# H0AR6_Frontend.net
KiCad netlist of a schematic drawn in Altium Designer
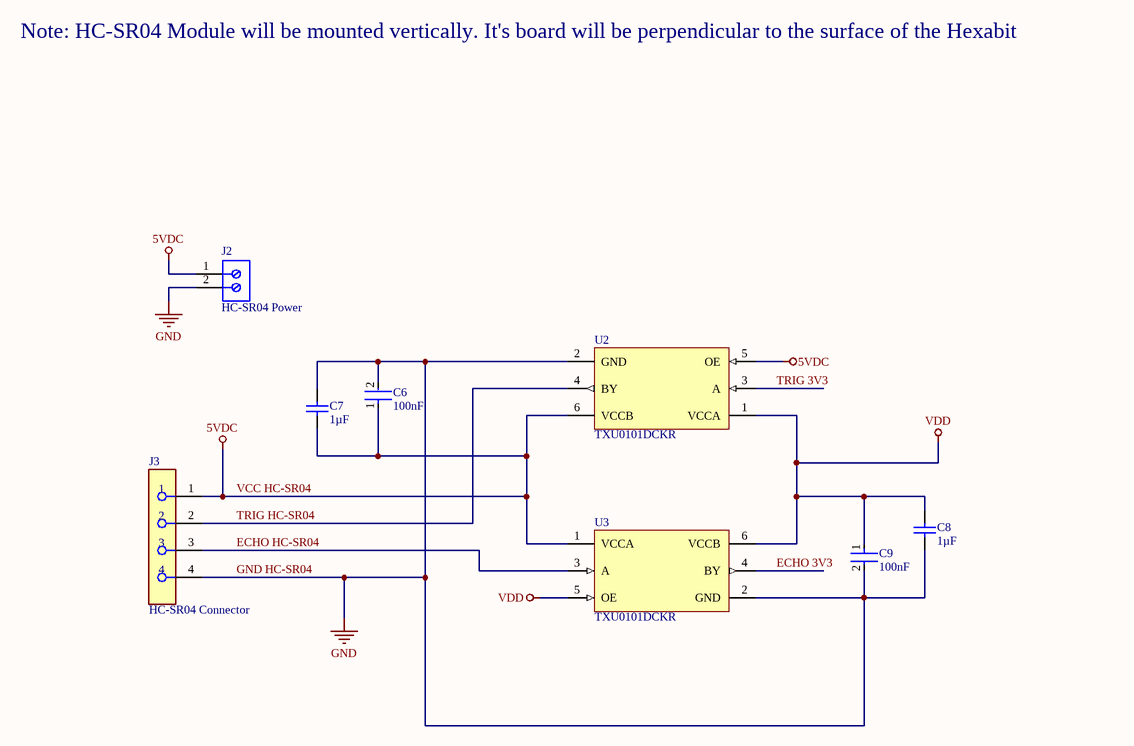
[diagram p0: H0AR6_Frontend.SchDoc]

(export (version "E")
  (design (tool "Eeschema 10.0.6"))
  (components
    (comp (ref "C6")
      (value "100nF")
      (footprint "FP-0603-L_1_6_0_15-W_0_81-MFG")
      (description "General Purpose Ceramic Capacitor, 0603, 100nF, 10%, X7R, 15%, 50V")
      (fields (field (name "TOLERANCE") "10%") (field (name "VOLTAGE") "50V"))
      (libsource (lib "Altium Content Vault") (part "02cd4be3c70576c341d710602a673aa"))
    )
    (comp (ref "C7")
      (value "1µF")
      (footprint "CAPC1608X90X35LL15T15")
      (fields
        (field (name "MANUFACTURER") "Kemet")
        (field (name "PART NUMBER") "C0603C105K4RACTU")
        (field (name "TOLERANCE") "10%")
      )
      (libsource (lib "Altium Content Vault") (part "CAP"))
    )
    (comp (ref "C8")
      (value "1µF")
      (footprint "CAPC1608X90X35LL15T15")
      (fields
        (field (name "MANUFACTURER") "Kemet")
        (field (name "PART NUMBER") "C0603C105K4RACTU")
        (field (name "TOLERANCE") "10%")
      )
      (libsource (lib "Altium Content Vault") (part "CAP"))
    )
    (comp (ref "C9")
      (value "100nF")
      (footprint "FP-0603-L_1_6_0_15-W_0_81-MFG")
      (description "General Purpose Ceramic Capacitor, 0603, 100nF, 10%, X7R, 15%, 50V")
      (fields (field (name "TOLERANCE") "10%") (field (name "VOLTAGE") "50V"))
      (libsource (lib "Altium Content Vault") (part "02cd4be3c70576c341d710602a673aa"))
    )
    (comp (ref "J2")
      (value "HC-SR04 Power")
      (footprint "691214110002")
      (fields (field (name "VOLTAGE") "300V"))
      (libsource (lib "Altium Content Vault") (part "TBL - 1R - 02P - Screw"))
    )
    (comp (ref "J3")
      (value "HC-SR04 Connector")
      (footprint "FP-SSW-104-02-G-S-MFG")
      (fields
        (field (name "MANUFACTURER") "Samtec")
        (field (name "MANUFACTURER PART NUMBER") "SSW-104-02-G-S")
      )
      (libsource (lib "Altium Content Vault") (part "56792406a6bd5c25e158f553ecd1aa7"))
    )
    (comp (ref "U2")
      (value "TXU0101DCKR")
      (footprint "FP-DCK0006A-MFG")
      (description "Single channel fixed-direction level shifter 6-SC70 -40 to 125")
      (fields (field (name "MANUFACTURER") "Texas Instruments"))
      (libsource (lib "") (part "TXU0101DCKR_1"))
    )
    (comp (ref "U3")
      (value "TXU0101DCKR")
      (footprint "FP-DCK0006A-MFG")
      (description "Single channel fixed-direction level shifter 6-SC70 -40 to 125")
      (fields (field (name "MANUFACTURER") "Texas Instruments"))
      (libsource (lib "Altium Content Vault") (part "TXU0101DCKR"))
    )
  )
  (nets
    (net (code "1") (name "/ECHO 3V3") (class "Default")
      (node (ref "U3") (pin "4") (pinfunction "BY_4") (pintype "output"))
    )
    (net (code "2") (name "/ECHO HC-SR04") (class "Default")
      (node (ref "J3") (pin "3") (pinfunction "3_3") (pintype "passive"))
      (node (ref "U3") (pin "3") (pinfunction "A_3") (pintype "input"))
    )
    (net (code "3") (name "/TRIG 3V3") (class "Default")
      (node (ref "U2") (pin "3") (pinfunction "A_3") (pintype "input"))
    )
    (net (code "4") (name "/TRIG HC-SR04") (class "Default")
      (node (ref "J3") (pin "2") (pinfunction "2_2") (pintype "passive"))
      (node (ref "U2") (pin "4") (pinfunction "BY_4") (pintype "output"))
    )
    (net (code "5") (name "5VDC") (class "Default")
      (node (ref "C6") (pin "1") (pinfunction "1_1") (pintype "passive"))
      (node (ref "C7") (pin "1") (pinfunction "1_1") (pintype "passive"))
      (node (ref "J2") (pin "1") (pinfunction "1_1") (pintype "passive"))
      (node (ref "J3") (pin "1") (pinfunction "1_1") (pintype "passive"))
      (node (ref "U2") (pin "5") (pinfunction "OE_5") (pintype "input"))
      (node (ref "U2") (pin "6") (pinfunction "VCCB_6") (pintype "power_in"))
      (node (ref "U3") (pin "1") (pinfunction "VCCA_1") (pintype "power_in"))
    )
    (net (code "6") (name "GND") (class "Default")
      (node (ref "C6") (pin "2") (pinfunction "2_2") (pintype "passive"))
      (node (ref "C7") (pin "2") (pinfunction "2_2") (pintype "passive"))
      (node (ref "C8") (pin "2") (pinfunction "2_2") (pintype "passive"))
      (node (ref "C9") (pin "2") (pinfunction "2_2") (pintype "passive"))
      (node (ref "J2") (pin "2") (pinfunction "2_2") (pintype "passive"))
      (node (ref "J3") (pin "4") (pinfunction "4_4") (pintype "passive"))
      (node (ref "U2") (pin "2") (pinfunction "GND_2") (pintype "power_in"))
      (node (ref "U3") (pin "2") (pinfunction "GND_2") (pintype "power_in"))
    )
    (net (code "7") (name "VDD") (class "Default")
      (node (ref "C8") (pin "1") (pinfunction "1_1") (pintype "passive"))
      (node (ref "C9") (pin "1") (pinfunction "1_1") (pintype "passive"))
      (node (ref "U2") (pin "1") (pinfunction "VCCA_1") (pintype "power_in"))
      (node (ref "U3") (pin "5") (pinfunction "OE_5") (pintype "input"))
      (node (ref "U3") (pin "6") (pinfunction "VCCB_6") (pintype "power_in"))
    )
  )
)
